# SCH_pcb-card_2024-03-10.net
KiCad netlist of a schematic drawn in EasyEDA
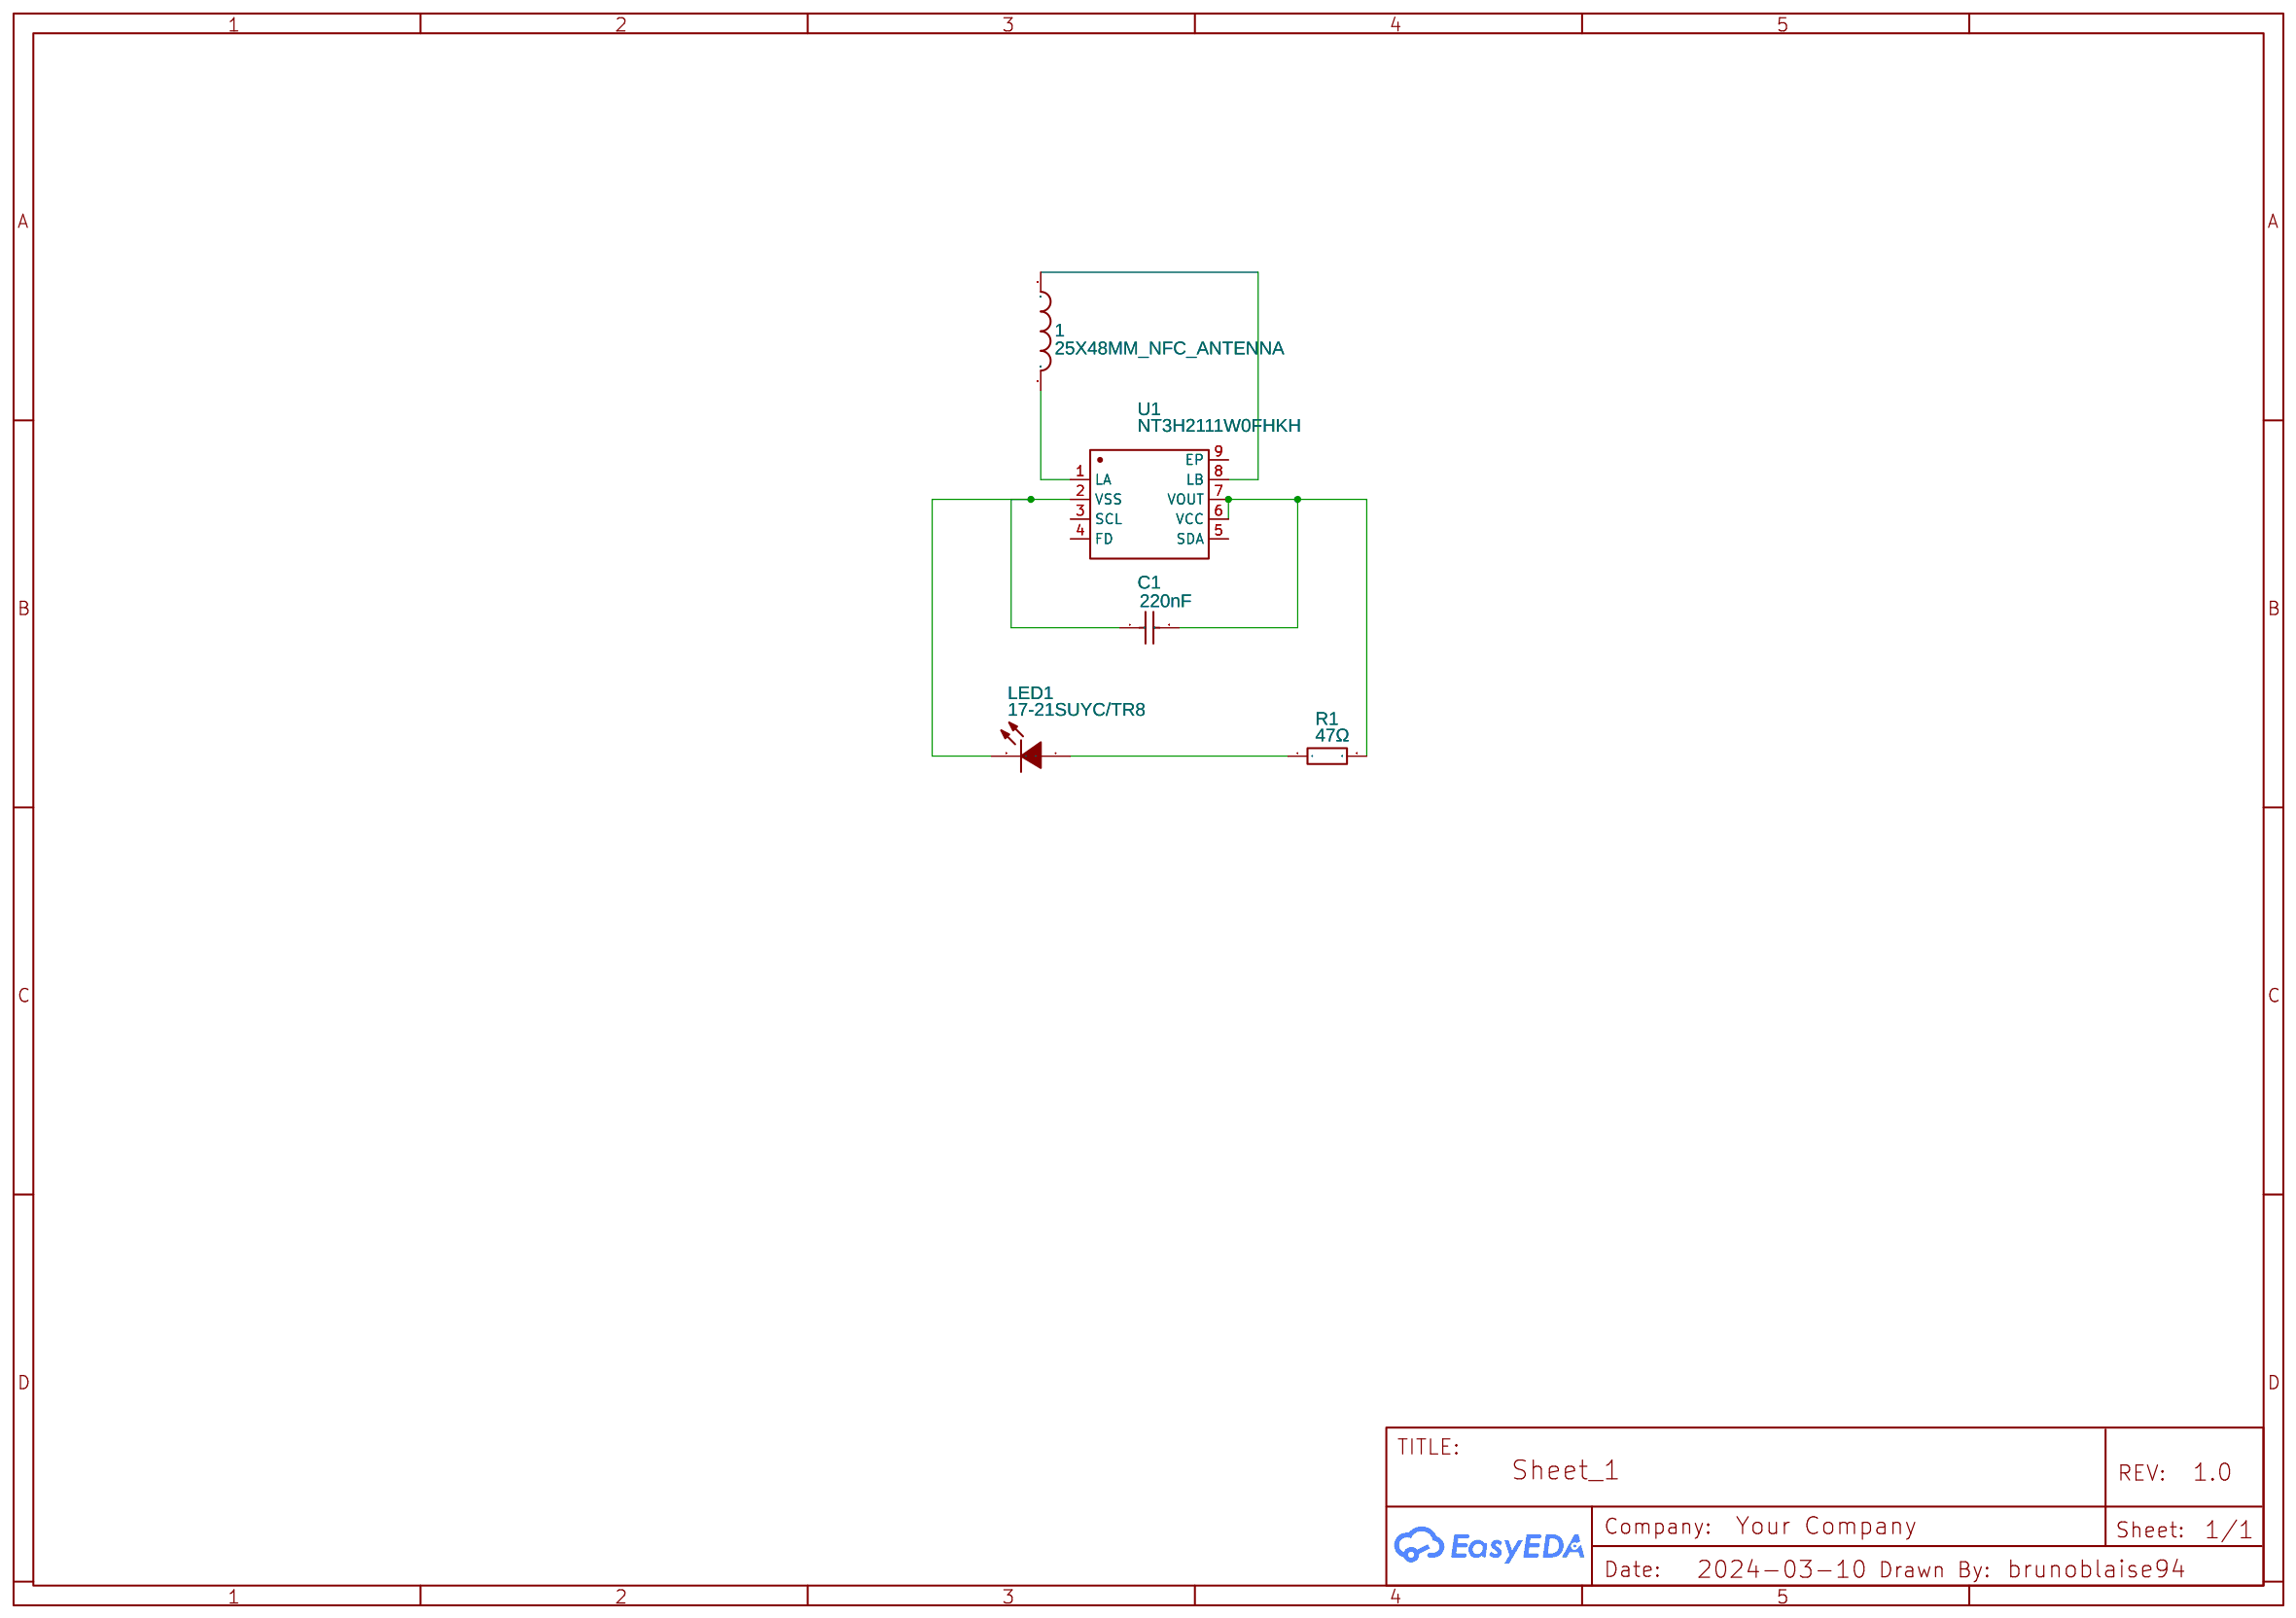
[diagram p0: schematic sheet]

(export (version "E")
  (design (tool "Eeschema 10.0.6"))
  (components
    (comp (ref "1") (value "25X48MM_NFC_ANTENNA") (libsource (lib "") (part "25X48MM_NFC_ANTENNA")))
    (comp (ref "C1")
      (value "220nF")
      (fields
        (field (name "Manufacturer Part") "CL10B224KA8NNNC")
        (field (name "Manufacturer") "SAMSUNG(三星)")
      )
      (libsource (lib "") (part "CL10B224KA8NNNC"))
    )
    (comp (ref "LED1")
      (value "17-21SUYC/TR8")
      (fields (field (name "Manufacturer Part") "KT-0805黄灯") (field (name "Manufacturer") "KENTO"))
      (libsource (lib "") (part "17-21SUYC/TR8"))
    )
    (comp (ref "R1")
      (value "47Ω")
      (fields
        (field (name "Manufacturer Part") "0603WAF470JT5E")
        (field (name "Manufacturer") "UNI-ROYAL(厚声)")
      )
      (libsource (lib "") (part "0603WAF470JT5E"))
    )
    (comp (ref "U1")
      (value "NT3H2111W0FHKH")
      (fields (field (name "Manufacturer") "NXP(恩智浦)"))
      (libsource (lib "") (part "NT3H2111W0FHKH"))
    )
  )
  (nets
    (net (code "1") (name "Net-(LED1-+)") (class "Default")
      (node (ref "LED1") (pin "1") (pinfunction "+_1") (pintype "unspecified"))
      (node (ref "R1") (pin "1") (pinfunction "1_1") (pintype "input"))
    )
    (net (code "2") (name "Net-(LED1--)") (class "Default")
      (node (ref "C1") (pin "1") (pinfunction "1_1") (pintype "input"))
      (node (ref "LED1") (pin "2") (pinfunction "-_2") (pintype "unspecified"))
      (node (ref "U1") (pin "2") (pinfunction "VSS_2") (pintype "unspecified"))
    )
    (net (code "3") (name "Net-(U1-LA)") (class "Default")
      (node (ref "1") (pin "P$2") (pinfunction "P$2_P$2") (pintype "bidirectional"))
      (node (ref "U1") (pin "1") (pinfunction "LA_1") (pintype "unspecified"))
    )
    (net (code "4") (name "Net-(U1-LB)") (class "Default")
      (node (ref "1") (pin "P$1") (pinfunction "P$1_P$1") (pintype "bidirectional"))
      (node (ref "U1") (pin "8") (pinfunction "LB_8") (pintype "unspecified"))
    )
    (net (code "5") (name "Net-(U1-VCC)") (class "Default")
      (node (ref "C1") (pin "2") (pinfunction "2_2") (pintype "input"))
      (node (ref "R1") (pin "2") (pinfunction "2_2") (pintype "input"))
      (node (ref "U1") (pin "6") (pinfunction "VCC_6") (pintype "unspecified"))
      (node (ref "U1") (pin "7") (pinfunction "VOUT_7") (pintype "unspecified"))
    )
    (net (code "6") (name "unconnected-(U1-EP-Pad9)") (class "Default")
      (node (ref "U1") (pin "9") (pinfunction "EP_9") (pintype "unspecified"))
    )
    (net (code "7") (name "unconnected-(U1-FD-Pad4)") (class "Default")
      (node (ref "U1") (pin "4") (pinfunction "FD_4") (pintype "unspecified"))
    )
    (net (code "8") (name "unconnected-(U1-SCL-Pad3)") (class "Default")
      (node (ref "U1") (pin "3") (pinfunction "SCL_3") (pintype "unspecified"))
    )
    (net (code "9") (name "unconnected-(U1-SDA-Pad5)") (class "Default")
      (node (ref "U1") (pin "5") (pinfunction "SDA_5") (pintype "unspecified"))
    )
  )
)
